# button.net
KiCad netlist of a schematic drawn in EAGLE
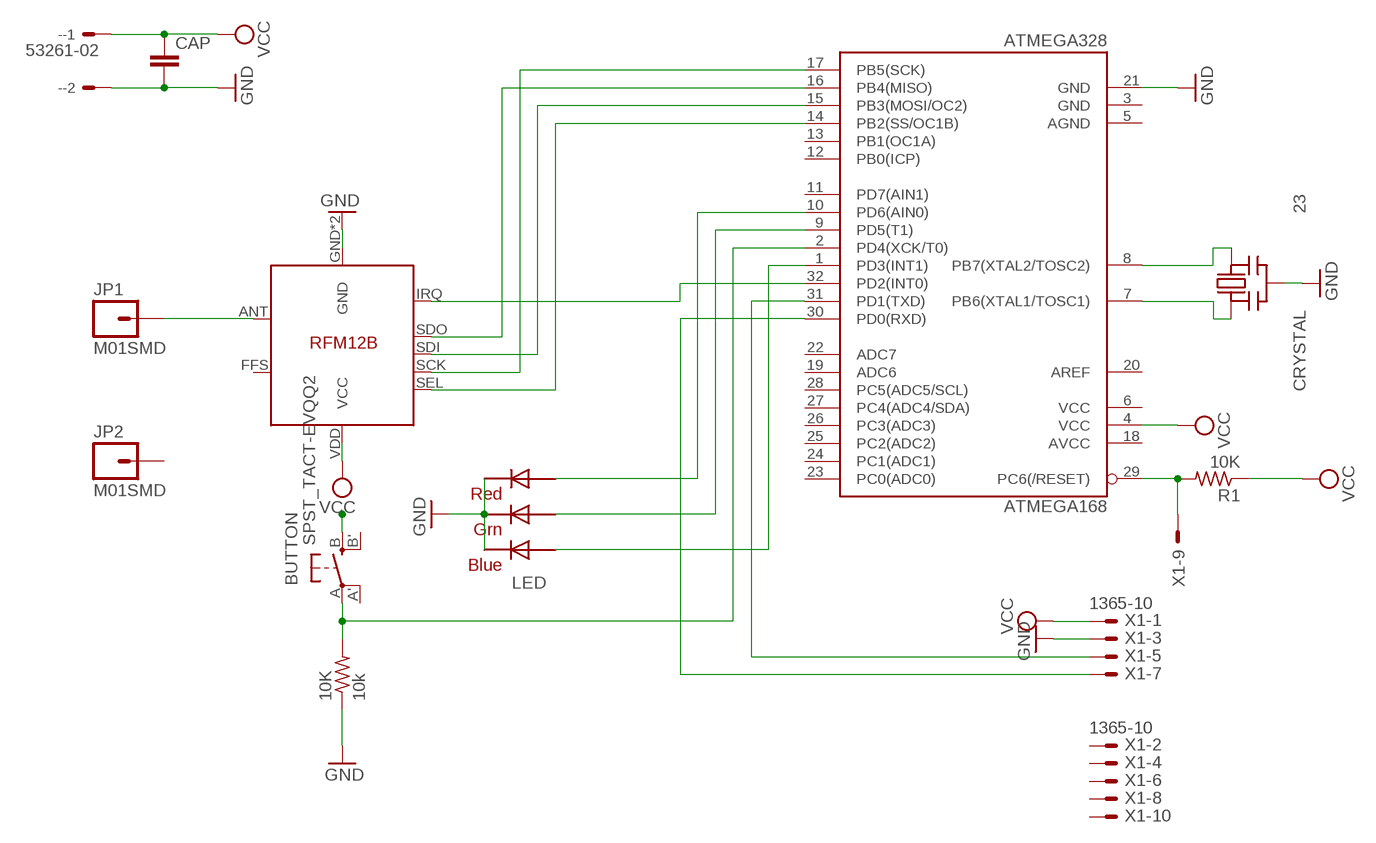
[diagram p0: schematic, sheet 1]

(export (version "E")
  (design (tool "Eeschema 10.0.6"))
  (components
    (comp (ref "-")
      (value "53261-02")
      (footprint "eagle-import:53261-02")
      (libsource (lib "eagle-import") (part "53?-02261"))
    )
    (comp (ref "10K")
      (value "10k")
      (footprint "eagle-import:R1206")
      (libsource (lib "eagle-import") (part "R-US_R1206"))
    )
    (comp (ref "ATMEGA328")
      (value "ATMEGA168")
      (footprint "eagle-import:TQFP32-08")
      (libsource (lib "eagle-import") (part "ATMEGA168"))
    )
    (comp (ref "BUTTON")
      (value "SPST_TACT-EVQQ2")
      (footprint "eagle-import:EVQ-Q2")
      (libsource (lib "eagle-import") (part "SPST_TACT-EVQQ2"))
    )
    (comp (ref "CAP")
      (value "CAP1206")
      (footprint "eagle-import:1206")
      (libsource (lib "eagle-import") (part "CAP1206"))
    )
    (comp (ref "CRYSTAL")
      (value "23")
      (footprint "eagle-import:CSTCR-G")
      (libsource (lib "eagle-import") (part "CERMOSCILL-CSTCRG"))
    )
    (comp (ref "JP1")
      (value "M01SMD")
      (footprint "eagle-import:LUXEON-PAD")
      (libsource (lib "eagle-import") (part "M01SMD"))
    )
    (comp (ref "JP2")
      (value "M01SMD")
      (footprint "eagle-import:LUXEON-PAD")
      (libsource (lib "eagle-import") (part "M01SMD"))
    )
    (comp (ref "LED")
      (value "RGBLED5050")
      (footprint "eagle-import:RGBLED5050")
      (libsource (lib "eagle-import") (part "RGBLED5050"))
    )
    (comp (ref "R1")
      (value "10K")
      (footprint "eagle-import:R1206")
      (libsource (lib "eagle-import") (part "R-US_R1206"))
    )
    (comp (ref "RFM12B")
      (value "RFM12B")
      (footprint "eagle-import:RFM12B")
      (libsource (lib "eagle-import") (part "RFM12BRMF12BGND"))
    )
    (comp (ref "X1")
      (value "1365-10")
      (footprint "eagle-import:1365-10")
      (libsource (lib "eagle-import") (part "1365-10"))
    )
  )
  (nets
    (net (code "1") (name "GND") (class "Default")
      (node (ref "-") (pin "2") (pinfunction "S_2") (pintype "passive"))
      (node (ref "10K") (pin "1") (pinfunction "1_1") (pintype "passive"))
      (node (ref "ATMEGA328") (pin "21") (pinfunction "GND_21") (pintype "bidirectional"))
      (node (ref "CAP") (pin "2") (pinfunction "2_2") (pintype "passive"))
      (node (ref "CRYSTAL") (pin "2") (pinfunction "GND_2") (pintype "bidirectional"))
      (node (ref "LED") (pin "4") (pinfunction "BLUE_C_4") (pintype "bidirectional"))
      (node (ref "LED") (pin "5") (pinfunction "RED_C_5") (pintype "bidirectional"))
      (node (ref "LED") (pin "6") (pinfunction "GREEN_C_6") (pintype "bidirectional"))
      (node (ref "RFM12B") (pin "GND") (pinfunction "GND_GND") (pintype "power_in"))
      (node (ref "RFM12B") (pin "P$12") (pinfunction "GND_P$12") (pintype "power_in"))
      (node (ref "X1") (pin "3") (pinfunction "S_3") (pintype "passive"))
    )
    (net (code "2") (name "Net-(ATMEGA328-PB2(SS{slash}OC1B))") (class "Default")
      (node (ref "ATMEGA328") (pin "14") (pinfunction "PB2(SS/OC1B)_14") (pintype "bidirectional"))
      (node (ref "RFM12B") (pin "SEL") (pinfunction "SEL_SEL") (pintype "input"))
    )
    (net (code "3") (name "Net-(ATMEGA328-PB3(MOSI{slash}OC2))") (class "Default")
      (node (ref "ATMEGA328") (pin "15") (pinfunction "PB3(MOSI/OC2)_15") (pintype "bidirectional"))
      (node (ref "RFM12B") (pin "SDI") (pinfunction "SDI_SDI") (pintype "input"))
    )
    (net (code "4") (name "Net-(ATMEGA328-PB4(MISO))") (class "Default")
      (node (ref "ATMEGA328") (pin "16") (pinfunction "PB4(MISO)_16") (pintype "bidirectional"))
      (node (ref "RFM12B") (pin "SDO") (pinfunction "SDO_SDO") (pintype "output"))
    )
    (net (code "5") (name "Net-(ATMEGA328-PB5(SCK))") (class "Default")
      (node (ref "ATMEGA328") (pin "17") (pinfunction "PB5(SCK)_17") (pintype "bidirectional"))
      (node (ref "RFM12B") (pin "SCK") (pinfunction "SCK_SCK") (pintype "input"))
    )
    (net (code "6") (name "Net-(ATMEGA328-PB6(XTAL1{slash}TOSC1))") (class "Default")
      (node (ref "ATMEGA328") (pin "7") (pinfunction "PB6(XTAL1/TOSC1)_7") (pintype "bidirectional"))
      (node (ref "CRYSTAL") (pin "1") (pinfunction "IN_1") (pintype "bidirectional"))
    )
    (net (code "7") (name "Net-(ATMEGA328-PB7(XTAL2{slash}TOSC2))") (class "Default")
      (node (ref "ATMEGA328") (pin "8") (pinfunction "PB7(XTAL2/TOSC2)_8") (pintype "bidirectional"))
      (node (ref "CRYSTAL") (pin "3") (pinfunction "OUT_3") (pintype "bidirectional"))
    )
    (net (code "8") (name "Net-(ATMEGA328-PC6({slash}RESET))") (class "Default")
      (node (ref "ATMEGA328") (pin "29") (pinfunction "PC6(/RESET)_29") (pintype "bidirectional"))
      (node (ref "R1") (pin "2") (pinfunction "2_2") (pintype "passive"))
      (node (ref "X1") (pin "9") (pinfunction "S_9") (pintype "passive"))
    )
    (net (code "9") (name "Net-(ATMEGA328-PD0(RXD))") (class "Default")
      (node (ref "ATMEGA328") (pin "30") (pinfunction "PD0(RXD)_30") (pintype "bidirectional"))
      (node (ref "X1") (pin "7") (pinfunction "S_7") (pintype "passive"))
    )
    (net (code "10") (name "Net-(ATMEGA328-PD1(TXD))") (class "Default")
      (node (ref "ATMEGA328") (pin "31") (pinfunction "PD1(TXD)_31") (pintype "bidirectional"))
      (node (ref "X1") (pin "5") (pinfunction "S_5") (pintype "passive"))
    )
    (net (code "11") (name "Net-(ATMEGA328-PD2(INT0))") (class "Default")
      (node (ref "ATMEGA328") (pin "32") (pinfunction "PD2(INT0)_32") (pintype "bidirectional"))
      (node (ref "RFM12B") (pin "IRQ") (pinfunction "IRQ_IRQ") (pintype "open_collector"))
    )
    (net (code "12") (name "Net-(ATMEGA328-PD3(INT1))") (class "Default")
      (node (ref "ATMEGA328") (pin "1") (pinfunction "PD3(INT1)_1") (pintype "bidirectional"))
      (node (ref "LED") (pin "3") (pinfunction "BLUE_A_3") (pintype "bidirectional"))
    )
    (net (code "13") (name "Net-(ATMEGA328-PD4(XCK{slash}T0))") (class "Default")
      (node (ref "10K") (pin "2") (pinfunction "2_2") (pintype "passive"))
      (node (ref "ATMEGA328") (pin "2") (pinfunction "PD4(XCK/T0)_2") (pintype "bidirectional"))
      (node (ref "BUTTON") (pin "A") (pinfunction "P_A") (pintype "passive"))
    )
    (net (code "14") (name "Net-(ATMEGA328-PD5(T1))") (class "Default")
      (node (ref "ATMEGA328") (pin "9") (pinfunction "PD5(T1)_9") (pintype "bidirectional"))
      (node (ref "LED") (pin "1") (pinfunction "GREEN_A_1") (pintype "bidirectional"))
    )
    (net (code "15") (name "Net-(ATMEGA328-PD6(AIN0))") (class "Default")
      (node (ref "ATMEGA328") (pin "10") (pinfunction "PD6(AIN0)_10") (pintype "bidirectional"))
      (node (ref "LED") (pin "2") (pinfunction "RED_A_2") (pintype "bidirectional"))
    )
    (net (code "16") (name "Net-(JP1-1)") (class "Default")
      (node (ref "JP1") (pin "P$1") (pinfunction "1_P$1") (pintype "passive"))
      (node (ref "RFM12B") (pin "ANT") (pinfunction "ANT_ANT") (pintype "passive"))
    )
    (net (code "17") (name "VCC") (class "Default")
      (node (ref "-") (pin "1") (pinfunction "S_1") (pintype "passive"))
      (node (ref "ATMEGA328") (pin "4") (pinfunction "VCC_4") (pintype "bidirectional"))
      (node (ref "BUTTON") (pin "B") (pinfunction "S_B") (pintype "passive"))
      (node (ref "CAP") (pin "1") (pinfunction "1_1") (pintype "passive"))
      (node (ref "R1") (pin "1") (pinfunction "1_1") (pintype "passive"))
      (node (ref "RFM12B") (pin "VDD") (pinfunction "VCC_VDD") (pintype "power_in"))
      (node (ref "X1") (pin "1") (pinfunction "S_1") (pintype "passive"))
    )
    (net (code "18") (name "unconnected-(ATMEGA328-ADC6-Pad19)") (class "Default")
      (node (ref "ATMEGA328") (pin "19") (pinfunction "ADC6_19") (pintype "bidirectional"))
    )
    (net (code "19") (name "unconnected-(ATMEGA328-ADC7-Pad22)") (class "Default")
      (node (ref "ATMEGA328") (pin "22") (pinfunction "ADC7_22") (pintype "bidirectional"))
    )
    (net (code "20") (name "unconnected-(ATMEGA328-AGND-Pad5)") (class "Default")
      (node (ref "ATMEGA328") (pin "5") (pinfunction "AGND_5") (pintype "bidirectional"))
    )
    (net (code "21") (name "unconnected-(ATMEGA328-AREF-Pad20)") (class "Default")
      (node (ref "ATMEGA328") (pin "20") (pinfunction "AREF_20") (pintype "bidirectional"))
    )
    (net (code "22") (name "unconnected-(ATMEGA328-AVCC-Pad18)") (class "Default")
      (node (ref "ATMEGA328") (pin "18") (pinfunction "AVCC_18") (pintype "bidirectional"))
    )
    (net (code "23") (name "unconnected-(ATMEGA328-GND-Pad3)") (class "Default")
      (node (ref "ATMEGA328") (pin "3") (pinfunction "GND_3") (pintype "bidirectional"))
    )
    (net (code "24") (name "unconnected-(ATMEGA328-PB0(ICP)-Pad12)") (class "Default")
      (node (ref "ATMEGA328") (pin "12") (pinfunction "PB0(ICP)_12") (pintype "bidirectional"))
    )
    (net (code "25") (name "unconnected-(ATMEGA328-PB1(OC1A)-Pad13)") (class "Default")
      (node (ref "ATMEGA328") (pin "13") (pinfunction "PB1(OC1A)_13") (pintype "bidirectional"))
    )
    (net (code "26") (name "unconnected-(ATMEGA328-PC0(ADC0)-Pad23)") (class "Default")
      (node (ref "ATMEGA328") (pin "23") (pinfunction "PC0(ADC0)_23") (pintype "bidirectional"))
    )
    (net (code "27") (name "unconnected-(ATMEGA328-PC1(ADC1)-Pad24)") (class "Default")
      (node (ref "ATMEGA328") (pin "24") (pinfunction "PC1(ADC1)_24") (pintype "bidirectional"))
    )
    (net (code "28") (name "unconnected-(ATMEGA328-PC2(ADC2)-Pad25)") (class "Default")
      (node (ref "ATMEGA328") (pin "25") (pinfunction "PC2(ADC2)_25") (pintype "bidirectional"))
    )
    (net (code "29") (name "unconnected-(ATMEGA328-PC3(ADC3)-Pad26)") (class "Default")
      (node (ref "ATMEGA328") (pin "26") (pinfunction "PC3(ADC3)_26") (pintype "bidirectional"))
    )
    (net (code "30") (name "unconnected-(ATMEGA328-PC4(ADC4{slash}SDA)-Pad27)") (class "Default")
      (node (ref "ATMEGA328") (pin "27") (pinfunction "PC4(ADC4/SDA)_27") (pintype "bidirectional"))
    )
    (net (code "31") (name "unconnected-(ATMEGA328-PC5(ADC5{slash}SCL)-Pad28)") (class "Default")
      (node (ref "ATMEGA328") (pin "28") (pinfunction "PC5(ADC5/SCL)_28") (pintype "bidirectional"))
    )
    (net (code "32") (name "unconnected-(ATMEGA328-PD7(AIN1)-Pad11)") (class "Default")
      (node (ref "ATMEGA328") (pin "11") (pinfunction "PD7(AIN1)_11") (pintype "bidirectional"))
    )
    (net (code "33") (name "unconnected-(ATMEGA328-VCC-Pad6)") (class "Default")
      (node (ref "ATMEGA328") (pin "6") (pinfunction "VCC_6") (pintype "bidirectional"))
    )
    (net (code "34") (name "unconnected-(BUTTON-P1-PadA')") (class "Default")
      (node (ref "BUTTON") (pin "A'") (pinfunction "P1_A'") (pintype "passive"))
    )
    (net (code "35") (name "unconnected-(BUTTON-S1-PadB')") (class "Default")
      (node (ref "BUTTON") (pin "B'") (pinfunction "S1_B'") (pintype "passive"))
    )
    (net (code "36") (name "unconnected-(JP2-1-PadP$1)") (class "Default")
      (node (ref "JP2") (pin "P$1") (pinfunction "1_P$1") (pintype "passive"))
    )
    (net (code "37") (name "unconnected-(RFM12B-PadFFS)") (class "Default")
      (node (ref "RFM12B") (pin "FFS") (pinfunction "FFS_FFS") (pintype "bidirectional"))
    )
    (net (code "38") (name "unconnected-(X1B-S-Pad10)") (class "Default")
      (node (ref "X1") (pin "10") (pinfunction "S_10") (pintype "passive"))
    )
    (net (code "39") (name "unconnected-(X1C-S-Pad2)") (class "Default")
      (node (ref "X1") (pin "2") (pinfunction "S_2") (pintype "passive"))
    )
    (net (code "40") (name "unconnected-(X1E-S-Pad4)") (class "Default")
      (node (ref "X1") (pin "4") (pinfunction "S_4") (pintype "passive"))
    )
    (net (code "41") (name "unconnected-(X1G-S-Pad6)") (class "Default")
      (node (ref "X1") (pin "6") (pinfunction "S_6") (pintype "passive"))
    )
    (net (code "42") (name "unconnected-(X1I-S-Pad8)") (class "Default")
      (node (ref "X1") (pin "8") (pinfunction "S_8") (pintype "passive"))
    )
  )
)
